# mainBord_old.net
KiCad netlist of a schematic drawn in Altium Designer
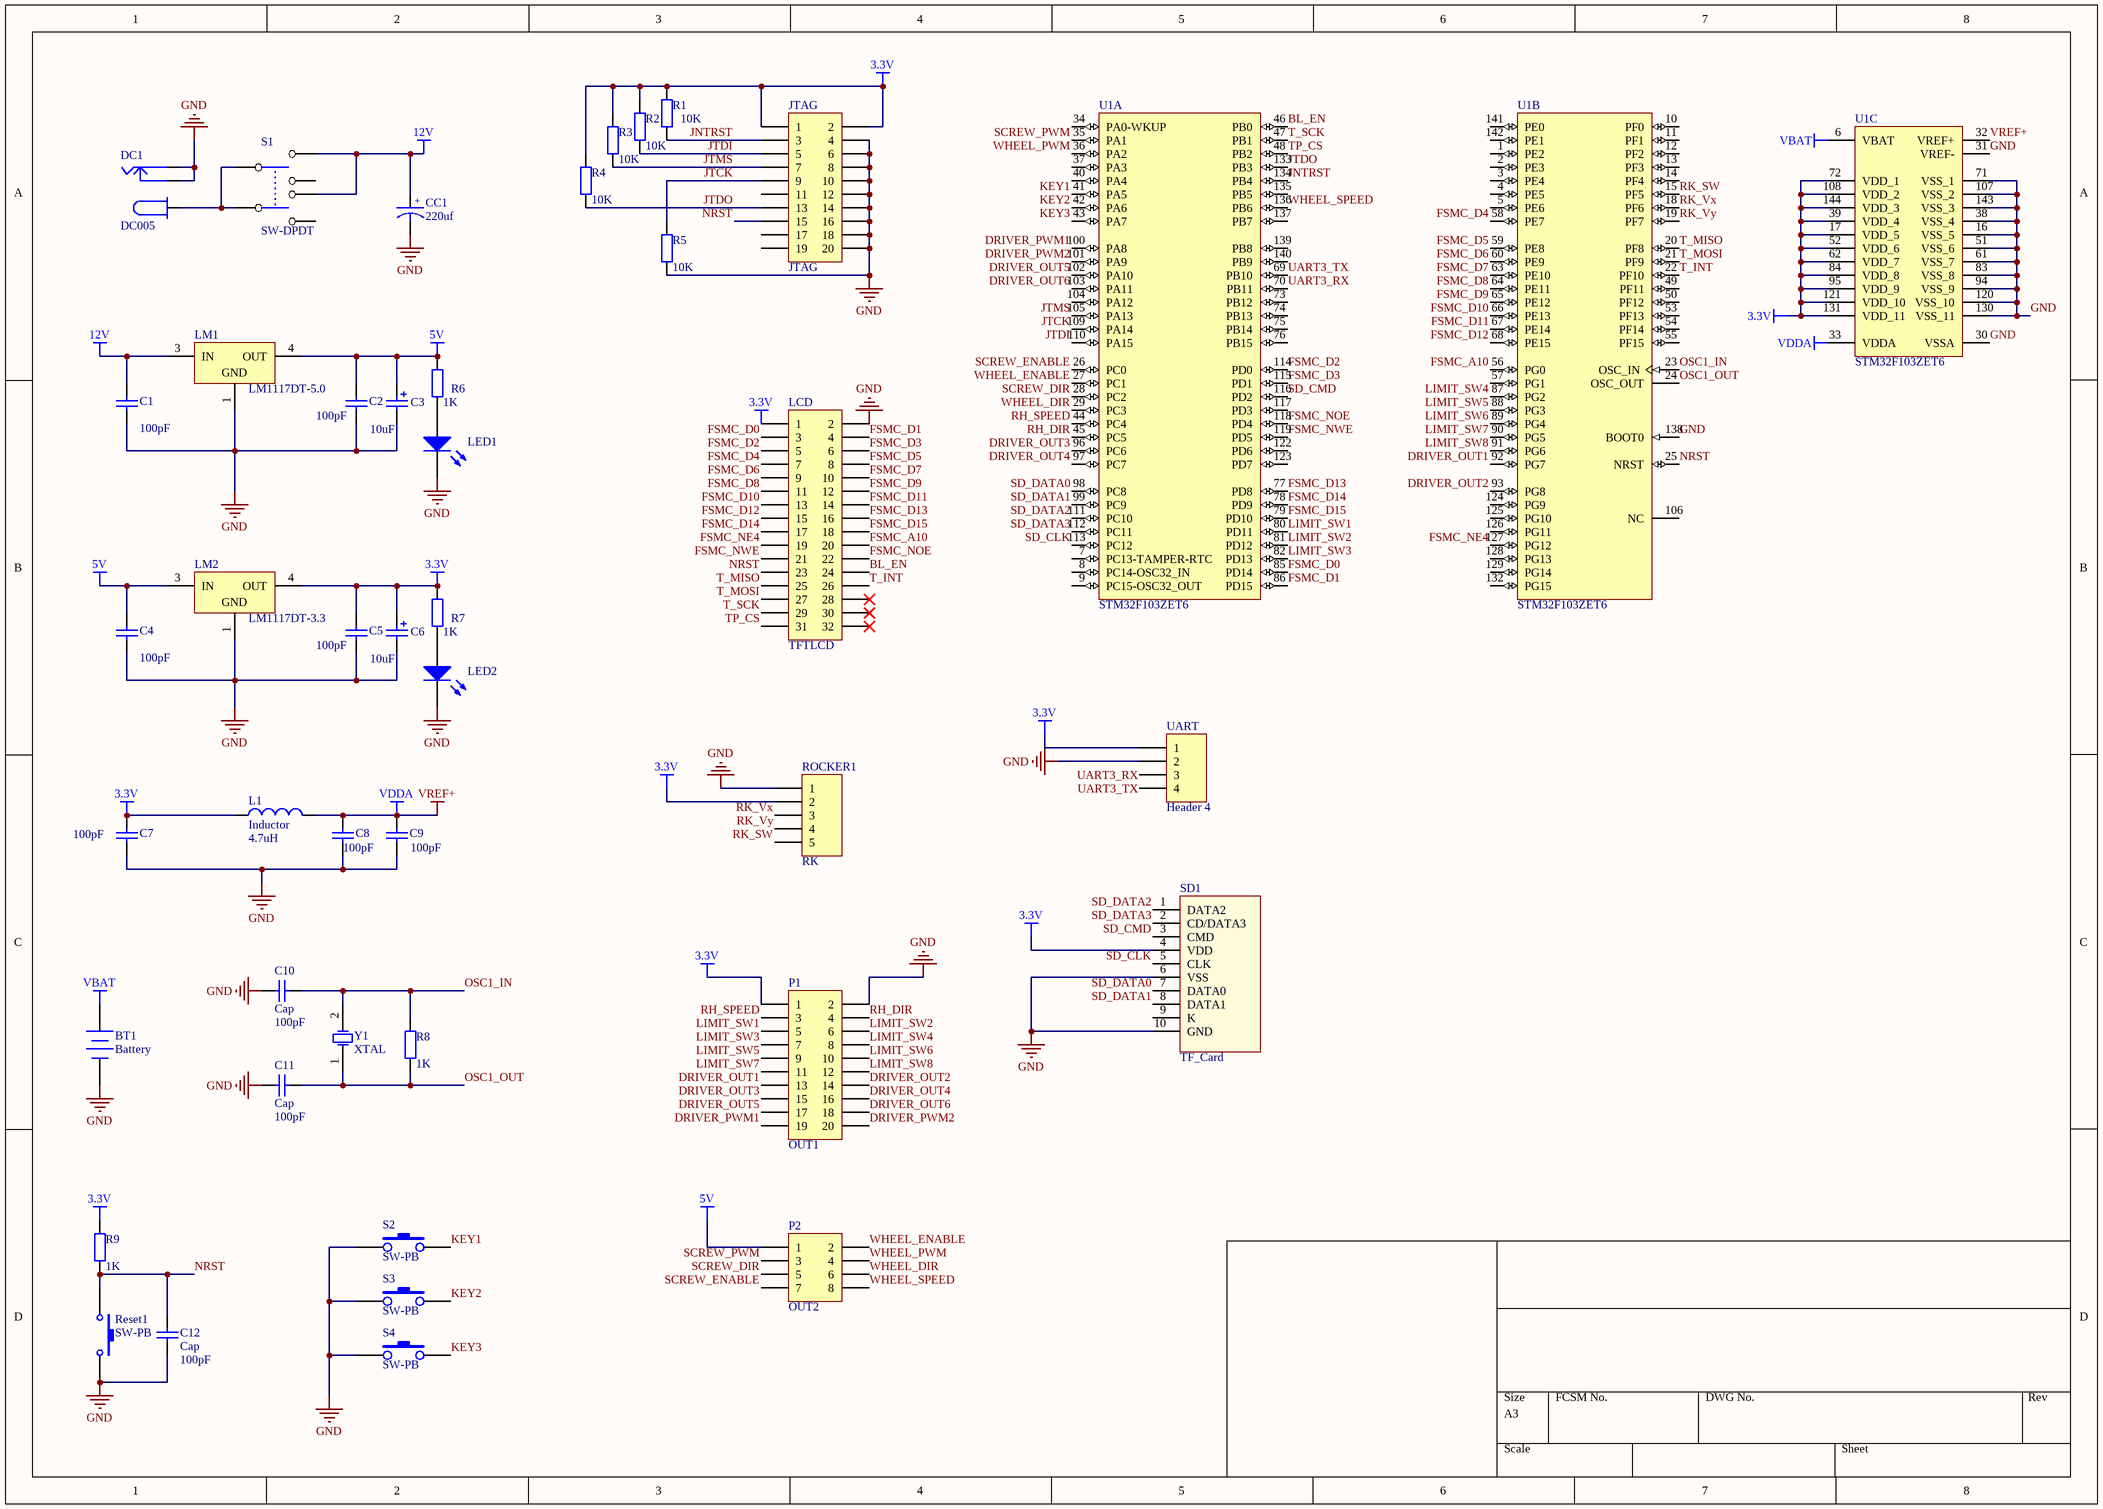
[diagram p0: mainBord_old.SchDoc]

(export (version "E")
  (design (tool "Eeschema 10.0.6"))
  (components
    (comp (ref "BT1")
      (value "Battery")
      (footprint "battery")
      (description "Multicell Battery")
      (fields (field (name "PUBLISHER") "Altium Limited"))
      (libsource (lib "Miscellaneous Devices") (part "Battery"))
    )
    (comp (ref "C1")
      (value "100pF")
      (footprint "C 0805_L")
      (description "Capacitor")
      (fields (field (name "Comment") "Cap") (field (name "PUBLISHER") "Altium Limited"))
      (libsource (lib "Miscellaneous Devices") (part "Cap"))
    )
    (comp (ref "C2")
      (value "100pF")
      (footprint "C 0805_L")
      (description "Capacitor")
      (fields (field (name "Comment") "Cap") (field (name "PUBLISHER") "Altium Limited"))
      (libsource (lib "Miscellaneous Devices") (part "Cap"))
    )
    (comp (ref "C3")
      (value "10uF")
      (footprint "CD A(3216)")
      (description "Polarized Capacitor (Axial)")
      (fields (field (name "Comment") "Cap Pol2") (field (name "PUBLISHER") "Altium Limited"))
      (libsource (lib "Miscellaneous Devices") (part "Cap Pol2"))
    )
    (comp (ref "C4")
      (value "100pF")
      (footprint "C 0805_L")
      (description "Capacitor")
      (fields (field (name "Comment") "Cap") (field (name "PUBLISHER") "Altium Limited"))
      (libsource (lib "Miscellaneous Devices") (part "Cap"))
    )
    (comp (ref "C5")
      (value "100pF")
      (footprint "C 0805_L")
      (description "Capacitor")
      (fields (field (name "Comment") "Cap") (field (name "PUBLISHER") "Altium Limited"))
      (libsource (lib "Miscellaneous Devices") (part "Cap"))
    )
    (comp (ref "C6")
      (value "10uF")
      (footprint "CD A(3216)")
      (description "Polarized Capacitor (Axial)")
      (fields (field (name "Comment") "Cap Pol2") (field (name "PUBLISHER") "Altium Limited"))
      (libsource (lib "Miscellaneous Devices") (part "Cap Pol2"))
    )
    (comp (ref "C7")
      (value "100pF")
      (footprint "C 0805_L")
      (description "Capacitor")
      (fields (field (name "Comment") "Cap") (field (name "PUBLISHER") "Altium Limited"))
      (libsource (lib "Miscellaneous Devices") (part "Cap"))
    )
    (comp (ref "C8")
      (value "100pF")
      (footprint "C 0805_L")
      (description "Capacitor")
      (fields (field (name "Comment") "Cap") (field (name "PUBLISHER") "Altium Limited"))
      (libsource (lib "Miscellaneous Devices") (part "Cap"))
    )
    (comp (ref "C9")
      (value "100pF")
      (footprint "C 0805_L")
      (description "Capacitor")
      (fields (field (name "Comment") "Cap") (field (name "PUBLISHER") "Altium Limited"))
      (libsource (lib "Miscellaneous Devices") (part "Cap"))
    )
    (comp (ref "C10")
      (value "Cap")
      (footprint "C 0805_L")
      (description "Capacitor")
      (fields (field (name "ALTIUM_VALUE") "100pF") (field (name "PUBLISHER") "Altium Limited"))
      (libsource (lib "Miscellaneous Devices") (part "Cap"))
    )
    (comp (ref "C11")
      (value "Cap")
      (footprint "C 0805_L")
      (description "Capacitor")
      (fields (field (name "ALTIUM_VALUE") "100pF") (field (name "PUBLISHER") "Altium Limited"))
      (libsource (lib "Miscellaneous Devices") (part "Cap"))
    )
    (comp (ref "C12")
      (value "Cap")
      (footprint "C 0805_L")
      (description "Capacitor")
      (fields (field (name "ALTIUM_VALUE") "100pF") (field (name "PUBLISHER") "Altium Limited"))
      (libsource (lib "Miscellaneous Devices") (part "Cap"))
    )
    (comp (ref "CC1")
      (value "220uf")
      (footprint "CC88")
      (description "钽电容")
      (libsource (lib "常用器件") (part "CAP-T"))
    )
    (comp (ref "DC1") (value "DC005") (footprint "DC005座") (libsource (lib "myLib") (part "DC005")))
    (comp (ref "JTAG")
      (value "JTAG")
      (footprint "JTAG20")
      (description "Header, 10-Pin, Dual row")
      (fields (field (name "PUBLISHER") "Altium Limited"))
      (libsource (lib "Miscellaneous Connectors") (part "Header 10X2"))
    )
    (comp (ref "L1")
      (value "Inductor")
      (footprint "L 0805")
      (fields (field (name "ALTIUM_VALUE") "4.7uH") (field (name "PUBLISHER") "Altium Limited"))
      (libsource (lib "Miscellaneous Devices") (part "Inductor"))
    )
    (comp (ref "LCD")
      (value "TFTLCD")
      (footprint "HDR2X16")
      (description "Header, 16-Pin, Dual row")
      (fields (field (name "PUBLISHER") "Altium Limited"))
      (libsource (lib "Miscellaneous Connectors") (part "MHDR2X16"))
    )
    (comp (ref "LED1")
      (value "LED2")
      (footprint "LED-0805")
      (description "Typical RED, GREEN, YELLOW, AMBER GaAs LED")
      (fields (field (name "PUBLISHER") "Altium Limited"))
      (libsource (lib "Miscellaneous Devices") (part "LED2"))
    )
    (comp (ref "LED2")
      (value "LED2")
      (footprint "LED-0805")
      (description "Typical RED, GREEN, YELLOW, AMBER GaAs LED")
      (fields (field (name "PUBLISHER") "Altium Limited"))
      (libsource (lib "Miscellaneous Devices") (part "LED2"))
    )
    (comp (ref "LM1")
      (value "LM1117DT-5.0")
      (footprint "SOT-223")
      (description "800mA Low-Dropout Linear Regulator, 3-pin TO-252")
      (fields (field (name "MANUFACTURER") "National Semiconductor"))
      (libsource (lib "National Semiconductor LDO") (part "LM1117DT-5.0"))
    )
    (comp (ref "LM2")
      (value "LM1117DT-3.3")
      (footprint "SOT-223")
      (description "800mA Low-Dropout Linear Regulator, 3-pin TO-252")
      (fields (field (name "MANUFACTURER") "National Semiconductor"))
      (libsource (lib "National Semiconductor LDO") (part "LM1117DT-3.3"))
    )
    (comp (ref "P1")
      (value "OUT1")
      (footprint "JTAG20")
      (description "Header, 10-Pin, Dual row")
      (fields (field (name "PUBLISHER") "Altium Limited"))
      (libsource (lib "Miscellaneous Connectors") (part "Header 10X2"))
    )
    (comp (ref "P2")
      (value "OUT2")
      (footprint "HDR2X4")
      (description "Header, 4-Pin, Dual row")
      (fields (field (name "PUBLISHER") "Altium Limited"))
      (libsource (lib "Miscellaneous Connectors") (part "Header 4X2"))
    )
    (comp (ref "R1")
      (value "10K")
      (footprint "R 0805_L")
      (description "Resistor")
      (fields (field (name "Comment") "Res2") (field (name "PUBLISHER") "Altium Limited"))
      (libsource (lib "Miscellaneous Devices") (part "Res2"))
    )
    (comp (ref "R2")
      (value "10K")
      (footprint "R 0805_L")
      (description "Resistor")
      (fields (field (name "PUBLISHER") "Altium Limited"))
      (libsource (lib "Miscellaneous Devices") (part "Res2"))
    )
    (comp (ref "R3")
      (value "10K")
      (footprint "R 0805_L")
      (description "Resistor")
      (fields (field (name "Comment") "Res2") (field (name "PUBLISHER") "Altium Limited"))
      (libsource (lib "Miscellaneous Devices") (part "Res2"))
    )
    (comp (ref "R4")
      (value "10K")
      (footprint "R 0805_L")
      (description "Resistor")
      (fields (field (name "Comment") "Res2") (field (name "PUBLISHER") "Altium Limited"))
      (libsource (lib "Miscellaneous Devices") (part "Res2"))
    )
    (comp (ref "R5")
      (value "10K")
      (footprint "R 0805_L")
      (description "Resistor")
      (fields (field (name "Comment") "Res2") (field (name "PUBLISHER") "Altium Limited"))
      (libsource (lib "Miscellaneous Devices") (part "Res2"))
    )
    (comp (ref "R6")
      (value "1K")
      (footprint "R 0805_L")
      (description "Resistor")
      (fields (field (name "Comment") "Res2") (field (name "PUBLISHER") "Altium Limited"))
      (libsource (lib "Miscellaneous Devices") (part "Res2"))
    )
    (comp (ref "R7")
      (value "1K")
      (footprint "R 0805_L")
      (description "Resistor")
      (fields (field (name "Comment") "Res2") (field (name "PUBLISHER") "Altium Limited"))
      (libsource (lib "Miscellaneous Devices") (part "Res2"))
    )
    (comp (ref "R8")
      (value "1K")
      (footprint "R 0805_L")
      (description "Resistor")
      (fields (field (name "Comment") "Res2") (field (name "PUBLISHER") "Altium Limited"))
      (libsource (lib "Miscellaneous Devices") (part "Res2"))
    )
    (comp (ref "R9")
      (value "1K")
      (footprint "R 0805_L")
      (description "Resistor")
      (fields (field (name "Comment") "Res2") (field (name "PUBLISHER") "Altium Limited"))
      (libsource (lib "Miscellaneous Devices") (part "Res2"))
    )
    (comp (ref "Reset1")
      (value "SW-PB")
      (footprint "微动开关-1")
      (description "Switch")
      (fields (field (name "PUBLISHER") "Altium Limited"))
      (libsource (lib "Miscellaneous Devices") (part "SW-PB"))
    )
    (comp (ref "ROCKER1")
      (value "RK")
      (footprint "HDR2.54-M-LI-5P")
      (description "Header, 5-Pin")
      (fields (field (name "PUBLISHER") "Altium Limited"))
      (libsource (lib "Miscellaneous Connectors") (part "MHDR1X5"))
    )
    (comp (ref "S1") (value "SW-DPDT") (footprint "按键开关-1") (libsource (lib "常用器件") (part "SW-DPDT")))
    (comp (ref "S2") (value "SW-PB") (footprint "微动开关-大-1-绿") (libsource (lib "常用器件") (part "微动开关")))
    (comp (ref "S3") (value "SW-PB") (footprint "微动开关-大-1-绿") (libsource (lib "常用器件") (part "微动开关")))
    (comp (ref "S4") (value "SW-PB") (footprint "微动开关-大-1-绿") (libsource (lib "常用器件") (part "微动开关")))
    (comp (ref "SD1")
      (value "TF_Card")
      (footprint "Micro SD")
      (description "TF卡座")
      (fields (field (name "版权归属") "源创客"))
      (libsource (lib "4.1   - 接口类") (part "TF_Card"))
    )
    (comp (ref "U1")
      (value "STM32F103ZET6")
      (footprint "STM-LQFP144_N")
      (libsource (lib "STMicroelectronics STM32 F1") (part "STM32F103ZET6"))
    )
    (comp (ref "UART")
      (value "Header 4")
      (footprint "HDR2.54-LI-4P")
      (description "Header, 4-Pin")
      (fields (field (name "PUBLISHER") "Altium Limited"))
      (libsource (lib "Miscellaneous Connectors") (part "Header 4"))
    )
    (comp (ref "Y1")
      (value "XTAL")
      (footprint "HC-49S")
      (description "Crystal Oscillator")
      (fields (field (name "PUBLISHER") "Altium Limited"))
      (libsource (lib "Miscellaneous Devices") (part "XTAL"))
    )
  )
  (nets
    (net (code "1") (name "/BL_EN") (class "Default")
      (node (ref "LCD") (pin "24") (pinfunction "24_24") (pintype "passive"))
      (node (ref "U1") (pin "46") (pinfunction "PB0_46") (pintype "bidirectional"))
    )
    (net (code "2") (name "/DRIVER_OUT1") (class "Default")
      (node (ref "P1") (pin "13") (pinfunction "13_13") (pintype "passive"))
      (node (ref "U1") (pin "92") (pinfunction "PG7_92") (pintype "bidirectional"))
    )
    (net (code "3") (name "/DRIVER_OUT2") (class "Default")
      (node (ref "P1") (pin "14") (pinfunction "14_14") (pintype "passive"))
      (node (ref "U1") (pin "93") (pinfunction "PG8_93") (pintype "bidirectional"))
    )
    (net (code "4") (name "/DRIVER_OUT3") (class "Default")
      (node (ref "P1") (pin "15") (pinfunction "15_15") (pintype "passive"))
      (node (ref "U1") (pin "96") (pinfunction "PC6_96") (pintype "bidirectional"))
    )
    (net (code "5") (name "/DRIVER_OUT4") (class "Default")
      (node (ref "P1") (pin "16") (pinfunction "16_16") (pintype "passive"))
      (node (ref "U1") (pin "97") (pinfunction "PC7_97") (pintype "bidirectional"))
    )
    (net (code "6") (name "/DRIVER_OUT5") (class "Default")
      (node (ref "P1") (pin "17") (pinfunction "17_17") (pintype "passive"))
      (node (ref "U1") (pin "102") (pinfunction "PA10_102") (pintype "bidirectional"))
    )
    (net (code "7") (name "/DRIVER_OUT6") (class "Default")
      (node (ref "P1") (pin "18") (pinfunction "18_18") (pintype "passive"))
      (node (ref "U1") (pin "103") (pinfunction "PA11_103") (pintype "bidirectional"))
    )
    (net (code "8") (name "/DRIVER_PWM1") (class "Default")
      (node (ref "P1") (pin "19") (pinfunction "19_19") (pintype "passive"))
      (node (ref "U1") (pin "100") (pinfunction "PA8_100") (pintype "bidirectional"))
    )
    (net (code "9") (name "/DRIVER_PWM2") (class "Default")
      (node (ref "P1") (pin "20") (pinfunction "20_20") (pintype "passive"))
      (node (ref "U1") (pin "101") (pinfunction "PA9_101") (pintype "bidirectional"))
    )
    (net (code "10") (name "/FSMC_A10") (class "Default")
      (node (ref "LCD") (pin "20") (pinfunction "20_20") (pintype "passive"))
      (node (ref "U1") (pin "56") (pinfunction "PG0_56") (pintype "bidirectional"))
    )
    (net (code "11") (name "/FSMC_D0") (class "Default")
      (node (ref "LCD") (pin "3") (pinfunction "3_3") (pintype "passive"))
      (node (ref "U1") (pin "85") (pinfunction "PD14_85") (pintype "bidirectional"))
    )
    (net (code "12") (name "/FSMC_D1") (class "Default")
      (node (ref "LCD") (pin "4") (pinfunction "4_4") (pintype "passive"))
      (node (ref "U1") (pin "86") (pinfunction "PD15_86") (pintype "bidirectional"))
    )
    (net (code "13") (name "/FSMC_D2") (class "Default")
      (node (ref "LCD") (pin "5") (pinfunction "5_5") (pintype "passive"))
      (node (ref "U1") (pin "114") (pinfunction "PD0_114") (pintype "bidirectional"))
    )
    (net (code "14") (name "/FSMC_D3") (class "Default")
      (node (ref "LCD") (pin "6") (pinfunction "6_6") (pintype "passive"))
      (node (ref "U1") (pin "115") (pinfunction "PD1_115") (pintype "bidirectional"))
    )
    (net (code "15") (name "/FSMC_D4") (class "Default")
      (node (ref "LCD") (pin "7") (pinfunction "7_7") (pintype "passive"))
      (node (ref "U1") (pin "58") (pinfunction "PE7_58") (pintype "bidirectional"))
    )
    (net (code "16") (name "/FSMC_D5") (class "Default")
      (node (ref "LCD") (pin "8") (pinfunction "8_8") (pintype "passive"))
      (node (ref "U1") (pin "59") (pinfunction "PE8_59") (pintype "bidirectional"))
    )
    (net (code "17") (name "/FSMC_D6") (class "Default")
      (node (ref "LCD") (pin "9") (pinfunction "9_9") (pintype "passive"))
      (node (ref "U1") (pin "60") (pinfunction "PE9_60") (pintype "bidirectional"))
    )
    (net (code "18") (name "/FSMC_D7") (class "Default")
      (node (ref "LCD") (pin "10") (pinfunction "10_10") (pintype "passive"))
      (node (ref "U1") (pin "63") (pinfunction "PE10_63") (pintype "bidirectional"))
    )
    (net (code "19") (name "/FSMC_D8") (class "Default")
      (node (ref "LCD") (pin "11") (pinfunction "11_11") (pintype "passive"))
      (node (ref "U1") (pin "64") (pinfunction "PE11_64") (pintype "bidirectional"))
    )
    (net (code "20") (name "/FSMC_D9") (class "Default")
      (node (ref "LCD") (pin "12") (pinfunction "12_12") (pintype "passive"))
      (node (ref "U1") (pin "65") (pinfunction "PE12_65") (pintype "bidirectional"))
    )
    (net (code "21") (name "/FSMC_D10") (class "Default")
      (node (ref "LCD") (pin "13") (pinfunction "13_13") (pintype "passive"))
      (node (ref "U1") (pin "66") (pinfunction "PE13_66") (pintype "bidirectional"))
    )
    (net (code "22") (name "/FSMC_D11") (class "Default")
      (node (ref "LCD") (pin "14") (pinfunction "14_14") (pintype "passive"))
      (node (ref "U1") (pin "67") (pinfunction "PE14_67") (pintype "bidirectional"))
    )
    (net (code "23") (name "/FSMC_D12") (class "Default")
      (node (ref "LCD") (pin "15") (pinfunction "15_15") (pintype "passive"))
      (node (ref "U1") (pin "68") (pinfunction "PE15_68") (pintype "bidirectional"))
    )
    (net (code "24") (name "/FSMC_D13") (class "Default")
      (node (ref "LCD") (pin "16") (pinfunction "16_16") (pintype "passive"))
      (node (ref "U1") (pin "77") (pinfunction "PD8_77") (pintype "bidirectional"))
    )
    (net (code "25") (name "/FSMC_D14") (class "Default")
      (node (ref "LCD") (pin "17") (pinfunction "17_17") (pintype "passive"))
      (node (ref "U1") (pin "78") (pinfunction "PD9_78") (pintype "bidirectional"))
    )
    (net (code "26") (name "/FSMC_D15") (class "Default")
      (node (ref "LCD") (pin "18") (pinfunction "18_18") (pintype "passive"))
      (node (ref "U1") (pin "79") (pinfunction "PD10_79") (pintype "bidirectional"))
    )
    (net (code "27") (name "/FSMC_NE4") (class "Default")
      (node (ref "LCD") (pin "19") (pinfunction "19_19") (pintype "passive"))
      (node (ref "U1") (pin "127") (pinfunction "PG12_127") (pintype "bidirectional"))
    )
    (net (code "28") (name "/FSMC_NOE") (class "Default")
      (node (ref "LCD") (pin "22") (pinfunction "22_22") (pintype "passive"))
      (node (ref "U1") (pin "118") (pinfunction "PD4_118") (pintype "bidirectional"))
    )
    (net (code "29") (name "/FSMC_NWE") (class "Default")
      (node (ref "LCD") (pin "21") (pinfunction "21_21") (pintype "passive"))
      (node (ref "U1") (pin "119") (pinfunction "PD5_119") (pintype "bidirectional"))
    )
    (net (code "30") (name "/JNTRST") (class "Default")
      (node (ref "JTAG") (pin "3") (pinfunction "3_3") (pintype "passive"))
      (node (ref "R1") (pin "1") (pinfunction "1_1") (pintype "passive"))
      (node (ref "U1") (pin "134") (pinfunction "PB4_134") (pintype "bidirectional"))
    )
    (net (code "31") (name "/JTCK") (class "Default")
      (node (ref "JTAG") (pin "9") (pinfunction "9_9") (pintype "passive"))
      (node (ref "R5") (pin "2") (pinfunction "2_2") (pintype "passive"))
      (node (ref "U1") (pin "109") (pinfunction "PA14_109") (pintype "bidirectional"))
    )
    (net (code "32") (name "/JTDI") (class "Default")
      (node (ref "JTAG") (pin "5") (pinfunction "5_5") (pintype "passive"))
      (node (ref "R2") (pin "1") (pinfunction "1_1") (pintype "passive"))
      (node (ref "U1") (pin "110") (pinfunction "PA15_110") (pintype "bidirectional"))
    )
    (net (code "33") (name "/JTDO") (class "Default")
      (node (ref "JTAG") (pin "13") (pinfunction "13_13") (pintype "passive"))
      (node (ref "R4") (pin "1") (pinfunction "1_1") (pintype "passive"))
      (node (ref "U1") (pin "133") (pinfunction "PB3_133") (pintype "bidirectional"))
    )
    (net (code "34") (name "/JTMS") (class "Default")
      (node (ref "JTAG") (pin "7") (pinfunction "7_7") (pintype "passive"))
      (node (ref "R3") (pin "1") (pinfunction "1_1") (pintype "passive"))
      (node (ref "U1") (pin "105") (pinfunction "PA13_105") (pintype "bidirectional"))
    )
    (net (code "35") (name "/KEY1") (class "Default")
      (node (ref "S2") (pin "2") (pinfunction "2_2") (pintype "passive"))
      (node (ref "U1") (pin "41") (pinfunction "PA5_41") (pintype "bidirectional"))
    )
    (net (code "36") (name "/KEY2") (class "Default")
      (node (ref "S3") (pin "2") (pinfunction "2_2") (pintype "passive"))
      (node (ref "U1") (pin "42") (pinfunction "PA6_42") (pintype "bidirectional"))
    )
    (net (code "37") (name "/KEY3") (class "Default")
      (node (ref "S4") (pin "2") (pinfunction "2_2") (pintype "passive"))
      (node (ref "U1") (pin "43") (pinfunction "PA7_43") (pintype "bidirectional"))
    )
    (net (code "38") (name "/LIMIT_SW1") (class "Default")
      (node (ref "P1") (pin "5") (pinfunction "5_5") (pintype "passive"))
      (node (ref "U1") (pin "80") (pinfunction "PD11_80") (pintype "bidirectional"))
    )
    (net (code "39") (name "/LIMIT_SW2") (class "Default")
      (node (ref "P1") (pin "6") (pinfunction "6_6") (pintype "passive"))
      (node (ref "U1") (pin "81") (pinfunction "PD12_81") (pintype "bidirectional"))
    )
    (net (code "40") (name "/LIMIT_SW3") (class "Default")
      (node (ref "P1") (pin "7") (pinfunction "7_7") (pintype "passive"))
      (node (ref "U1") (pin "82") (pinfunction "PD13_82") (pintype "bidirectional"))
    )
    (net (code "41") (name "/LIMIT_SW4") (class "Default")
      (node (ref "P1") (pin "8") (pinfunction "8_8") (pintype "passive"))
      (node (ref "U1") (pin "87") (pinfunction "PG2_87") (pintype "bidirectional"))
    )
    (net (code "42") (name "/LIMIT_SW5") (class "Default")
      (node (ref "P1") (pin "9") (pinfunction "9_9") (pintype "passive"))
      (node (ref "U1") (pin "88") (pinfunction "PG3_88") (pintype "bidirectional"))
    )
    (net (code "43") (name "/LIMIT_SW6") (class "Default")
      (node (ref "P1") (pin "10") (pinfunction "10_10") (pintype "passive"))
      (node (ref "U1") (pin "89") (pinfunction "PG4_89") (pintype "bidirectional"))
    )
    (net (code "44") (name "/LIMIT_SW7") (class "Default")
      (node (ref "P1") (pin "11") (pinfunction "11_11") (pintype "passive"))
      (node (ref "U1") (pin "90") (pinfunction "PG5_90") (pintype "bidirectional"))
    )
    (net (code "45") (name "/LIMIT_SW8") (class "Default")
      (node (ref "P1") (pin "12") (pinfunction "12_12") (pintype "passive"))
      (node (ref "U1") (pin "91") (pinfunction "PG6_91") (pintype "bidirectional"))
    )
    (net (code "46") (name "/NRST") (class "Default")
      (node (ref "C12") (pin "1") (pinfunction "1_1") (pintype "passive"))
      (node (ref "JTAG") (pin "15") (pinfunction "15_15") (pintype "passive"))
      (node (ref "LCD") (pin "23") (pinfunction "23_23") (pintype "passive"))
      (node (ref "R9") (pin "1") (pinfunction "1_1") (pintype "passive"))
      (node (ref "Reset1") (pin "1") (pinfunction "1_1") (pintype "passive"))
      (node (ref "U1") (pin "25") (pinfunction "NRST_25") (pintype "bidirectional"))
    )
    (net (code "47") (name "/OSC1_IN") (class "Default")
      (node (ref "C10") (pin "1") (pinfunction "1_1") (pintype "passive"))
      (node (ref "R8") (pin "2") (pinfunction "2_2") (pintype "passive"))
      (node (ref "U1") (pin "23") (pinfunction "OSC_IN_23") (pintype "input"))
      (node (ref "Y1") (pin "2") (pinfunction "OSC2_2") (pintype "passive"))
    )
    (net (code "48") (name "/OSC1_OUT") (class "Default")
      (node (ref "C11") (pin "1") (pinfunction "1_1") (pintype "passive"))
      (node (ref "R8") (pin "1") (pinfunction "1_1") (pintype "passive"))
      (node (ref "U1") (pin "24") (pinfunction "OSC_OUT_24") (pintype "passive"))
      (node (ref "Y1") (pin "1") (pinfunction "OSC1_1") (pintype "passive"))
    )
    (net (code "49") (name "/RH_DIR") (class "Default")
      (node (ref "P1") (pin "4") (pinfunction "4_4") (pintype "passive"))
      (node (ref "U1") (pin "45") (pinfunction "PC5_45") (pintype "bidirectional"))
    )
    (net (code "50") (name "/RH_SPEED") (class "Default")
      (node (ref "P1") (pin "3") (pinfunction "3_3") (pintype "passive"))
      (node (ref "U1") (pin "44") (pinfunction "PC4_44") (pintype "bidirectional"))
    )
    (net (code "51") (name "/RK_SW") (class "Default")
      (node (ref "ROCKER1") (pin "5") (pinfunction "5_5") (pintype "passive"))
      (node (ref "U1") (pin "15") (pinfunction "PF5_15") (pintype "bidirectional"))
    )
    (net (code "52") (name "/RK_Vx") (class "Default")
      (node (ref "ROCKER1") (pin "3") (pinfunction "3_3") (pintype "passive"))
      (node (ref "U1") (pin "18") (pinfunction "PF6_18") (pintype "bidirectional"))
    )
    (net (code "53") (name "/RK_Vy") (class "Default")
      (node (ref "ROCKER1") (pin "4") (pinfunction "4_4") (pintype "passive"))
      (node (ref "U1") (pin "19") (pinfunction "PF7_19") (pintype "bidirectional"))
    )
    (net (code "54") (name "/SCREW_DIR") (class "Default")
      (node (ref "P2") (pin "5") (pinfunction "5_5") (pintype "passive"))
      (node (ref "U1") (pin "28") (pinfunction "PC2_28") (pintype "bidirectional"))
    )
    (net (code "55") (name "/SCREW_ENABLE") (class "Default")
      (node (ref "P2") (pin "7") (pinfunction "7_7") (pintype "passive"))
      (node (ref "U1") (pin "26") (pinfunction "PC0_26") (pintype "bidirectional"))
    )
    (net (code "56") (name "/SCREW_PWM") (class "Default")
      (node (ref "P2") (pin "3") (pinfunction "3_3") (pintype "passive"))
      (node (ref "U1") (pin "35") (pinfunction "PA1_35") (pintype "bidirectional"))
    )
    (net (code "57") (name "/SD_CLK") (class "Default")
      (node (ref "SD1") (pin "5") (pinfunction "CLK_5") (pintype "passive"))
      (node (ref "U1") (pin "113") (pinfunction "PC12_113") (pintype "bidirectional"))
    )
    (net (code "58") (name "/SD_CMD") (class "Default")
      (node (ref "SD1") (pin "3") (pinfunction "CMD_3") (pintype "passive"))
      (node (ref "U1") (pin "116") (pinfunction "PD2_116") (pintype "bidirectional"))
    )
    (net (code "59") (name "/SD_DATA0") (class "Default")
      (node (ref "SD1") (pin "7") (pinfunction "DATA0_7") (pintype "passive"))
      (node (ref "U1") (pin "98") (pinfunction "PC8_98") (pintype "bidirectional"))
    )
    (net (code "60") (name "/SD_DATA1") (class "Default")
      (node (ref "SD1") (pin "8") (pinfunction "DATA1_8") (pintype "passive"))
      (node (ref "U1") (pin "99") (pinfunction "PC9_99") (pintype "bidirectional"))
    )
    (net (code "61") (name "/SD_DATA2") (class "Default")
      (node (ref "SD1") (pin "1") (pinfunction "DATA2_1") (pintype "passive"))
      (node (ref "U1") (pin "111") (pinfunction "PC10_111") (pintype "bidirectional"))
    )
    (net (code "62") (name "/SD_DATA3") (class "Default")
      (node (ref "SD1") (pin "2") (pinfunction "CD/DATA3_2") (pintype "passive"))
      (node (ref "U1") (pin "112") (pinfunction "PC11_112") (pintype "bidirectional"))
    )
    (net (code "63") (name "/TP_CS") (class "Default")
      (node (ref "LCD") (pin "31") (pinfunction "31_31") (pintype "passive"))
      (node (ref "U1") (pin "48") (pinfunction "PB2_48") (pintype "bidirectional"))
    )
    (net (code "64") (name "/T_INT") (class "Default")
      (node (ref "LCD") (pin "26") (pinfunction "26_26") (pintype "passive"))
      (node (ref "U1") (pin "22") (pinfunction "PF10_22") (pintype "bidirectional"))
    )
    (net (code "65") (name "/T_MISO") (class "Default")
      (node (ref "LCD") (pin "25") (pinfunction "25_25") (pintype "passive"))
      (node (ref "U1") (pin "20") (pinfunction "PF8_20") (pintype "bidirectional"))
    )
    (net (code "66") (name "/T_MOSI") (class "Default")
      (node (ref "LCD") (pin "27") (pinfunction "27_27") (pintype "passive"))
      (node (ref "U1") (pin "21") (pinfunction "PF9_21") (pintype "bidirectional"))
    )
    (net (code "67") (name "/T_SCK") (class "Default")
      (node (ref "LCD") (pin "29") (pinfunction "29_29") (pintype "passive"))
      (node (ref "U1") (pin "47") (pinfunction "PB1_47") (pintype "bidirectional"))
    )
    (net (code "68") (name "/UART3_RX") (class "Default")
      (node (ref "U1") (pin "70") (pinfunction "PB11_70") (pintype "bidirectional"))
      (node (ref "UART") (pin "3") (pinfunction "3_3") (pintype "passive"))
    )
    (net (code "69") (name "/UART3_TX") (class "Default")
      (node (ref "U1") (pin "69") (pinfunction "PB10_69") (pintype "bidirectional"))
      (node (ref "UART") (pin "4") (pinfunction "4_4") (pintype "passive"))
    )
    (net (code "70") (name "/WHEEL_DIR") (class "Default")
      (node (ref "P2") (pin "6") (pinfunction "6_6") (pintype "passive"))
      (node (ref "U1") (pin "29") (pinfunction "PC3_29") (pintype "bidirectional"))
    )
    (net (code "71") (name "/WHEEL_ENABLE") (class "Default")
      (node (ref "P2") (pin "2") (pinfunction "2_2") (pintype "passive"))
      (node (ref "U1") (pin "27") (pinfunction "PC1_27") (pintype "bidirectional"))
    )
    (net (code "72") (name "/WHEEL_PWM") (class "Default")
      (node (ref "P2") (pin "4") (pinfunction "4_4") (pintype "passive"))
      (node (ref "U1") (pin "36") (pinfunction "PA2_36") (pintype "bidirectional"))
    )
    (net (code "73") (name "/WHEEL_SPEED") (class "Default")
      (node (ref "P2") (pin "8") (pinfunction "8_8") (pintype "passive"))
      (node (ref "U1") (pin "136") (pinfunction "PB6_136") (pintype "bidirectional"))
    )
    (net (code "74") (name "3.3V") (class "Default")
      (node (ref "C5") (pin "2") (pinfunction "2_2") (pintype "passive"))
      (node (ref "C6") (pin "1") (pinfunction "1_1") (pintype "passive"))
      (node (ref "C7") (pin "2") (pinfunction "2_2") (pintype "passive"))
      (node (ref "JTAG") (pin "1") (pinfunction "1_1") (pintype "passive"))
      (node (ref "JTAG") (pin "2") (pinfunction "2_2") (pintype "passive"))
      (node (ref "L1") (pin "1") (pinfunction "1_1") (pintype "passive"))
      (node (ref "LCD") (pin "1") (pinfunction "1_1") (pintype "passive"))
      (node (ref "LM2") (pin "4") (pinfunction "OUT_4") (pintype "power_in"))
      (node (ref "P1") (pin "1") (pinfunction "1_1") (pintype "passive"))
      (node (ref "R1") (pin "2") (pinfunction "2_2") (pintype "passive"))
      (node (ref "R2") (pin "2") (pinfunction "2_2") (pintype "passive"))
      (node (ref "R3") (pin "2") (pinfunction "2_2") (pintype "passive"))
      (node (ref "R4") (pin "2") (pinfunction "2_2") (pintype "passive"))
      (node (ref "R7") (pin "2") (pinfunction "2_2") (pintype "passive"))
      (node (ref "R9") (pin "2") (pinfunction "2_2") (pintype "passive"))
      (node (ref "ROCKER1") (pin "2") (pinfunction "2_2") (pintype "passive"))
      (node (ref "SD1") (pin "4") (pinfunction "VDD_4") (pintype "passive"))
      (node (ref "U1") (pin "108") (pinfunction "VDD_2_108") (pintype "power_in"))
      (node (ref "U1") (pin "121") (pinfunction "VDD_10_121") (pintype "power_in"))
      (node (ref "U1") (pin "131") (pinfunction "VDD_11_131") (pintype "power_in"))
      (node (ref "U1") (pin "144") (pinfunction "VDD_3_144") (pintype "power_in"))
      (node (ref "U1") (pin "17") (pinfunction "VDD_5_17") (pintype "power_in"))
      (node (ref "U1") (pin "39") (pinfunction "VDD_4_39") (pintype "power_in"))
      (node (ref "U1") (pin "52") (pinfunction "VDD_6_52") (pintype "power_in"))
      (node (ref "U1") (pin "62") (pinfunction "VDD_7_62") (pintype "power_in"))
      (node (ref "U1") (pin "72") (pinfunction "VDD_1_72") (pintype "power_in"))
      (node (ref "U1") (pin "84") (pinfunction "VDD_8_84") (pintype "power_in"))
      (node (ref "U1") (pin "95") (pinfunction "VDD_9_95") (pintype "power_in"))
      (node (ref "UART") (pin "1") (pinfunction "1_1") (pintype "passive"))
    )
    (net (code "75") (name "5V") (class "Default")
      (node (ref "C2") (pin "2") (pinfunction "2_2") (pintype "passive"))
      (node (ref "C3") (pin "1") (pinfunction "1_1") (pintype "passive"))
      (node (ref "C4") (pin "2") (pinfunction "2_2") (pintype "passive"))
      (node (ref "LM1") (pin "4") (pinfunction "OUT_4") (pintype "power_in"))
      (node (ref "LM2") (pin "3") (pinfunction "IN_3") (pintype "power_in"))
      (node (ref "P2") (pin "1") (pinfunction "1_1") (pintype "passive"))
      (node (ref "R6") (pin "2") (pinfunction "2_2") (pintype "passive"))
    )
    (net (code "76") (name "12V") (class "Default")
      (node (ref "C1") (pin "2") (pinfunction "2_2") (pintype "passive"))
      (node (ref "CC1") (pin "1") (pinfunction "1_1") (pintype "passive"))
      (node (ref "LM1") (pin "3") (pinfunction "IN_3") (pintype "power_in"))
      (node (ref "S1") (pin "2") (pinfunction "2_2") (pintype "passive"))
      (node (ref "S1") (pin "5") (pinfunction "5_5") (pintype "passive"))
    )
    (net (code "77") (name "GND") (class "Default")
      (node (ref "BT1") (pin "2") (pinfunction "-_2") (pintype "passive"))
      (node (ref "C1") (pin "1") (pinfunction "1_1") (pintype "passive"))
      (node (ref "C10") (pin "2") (pinfunction "2_2") (pintype "passive"))
      (node (ref "C11") (pin "2") (pinfunction "2_2") (pintype "passive"))
      (node (ref "C12") (pin "2") (pinfunction "2_2") (pintype "passive"))
      (node (ref "C2") (pin "1") (pinfunction "1_1") (pintype "passive"))
      (node (ref "C3") (pin "2") (pinfunction "2_2") (pintype "passive"))
      (node (ref "C4") (pin "1") (pinfunction "1_1") (pintype "passive"))
      (node (ref "C5") (pin "1") (pinfunction "1_1") (pintype "passive"))
      (node (ref "C6") (pin "2") (pinfunction "2_2") (pintype "passive"))
      (node (ref "C7") (pin "1") (pinfunction "1_1") (pintype "passive"))
      (node (ref "C8") (pin "1") (pinfunction "1_1") (pintype "passive"))
      (node (ref "C9") (pin "1") (pinfunction "1_1") (pintype "passive"))
      (node (ref "CC1") (pin "2") (pinfunction "2_2") (pintype "passive"))
      (node (ref "DC1") (pin "CON") (pinfunction "SW_CON") (pintype "passive"))
      (node (ref "DC1") (pin "GND") (pinfunction "6_GND") (pintype "passive"))
      (node (ref "JTAG") (pin "10") (pinfunction "10_10") (pintype "passive"))
      (node (ref "JTAG") (pin "12") (pinfunction "12_12") (pintype "passive"))
      (node (ref "JTAG") (pin "14") (pinfunction "14_14") (pintype "passive"))
      (node (ref "JTAG") (pin "16") (pinfunction "16_16") (pintype "passive"))
      (node (ref "JTAG") (pin "18") (pinfunction "18_18") (pintype "passive"))
      (node (ref "JTAG") (pin "20") (pinfunction "20_20") (pintype "passive"))
      (node (ref "JTAG") (pin "4") (pinfunction "4_4") (pintype "passive"))
      (node (ref "JTAG") (pin "6") (pinfunction "6_6") (pintype "passive"))
      (node (ref "JTAG") (pin "8") (pinfunction "8_8") (pintype "passive"))
      (node (ref "LCD") (pin "2") (pinfunction "2_2") (pintype "passive"))
      (node (ref "LED1") (pin "2") (pinfunction "K_2") (pintype "passive"))
      (node (ref "LED2") (pin "2") (pinfunction "K_2") (pintype "passive"))
      (node (ref "LM1") (pin "1") (pinfunction "GND_1") (pintype "power_in"))
      (node (ref "LM2") (pin "1") (pinfunction "GND_1") (pintype "power_in"))
      (node (ref "P1") (pin "2") (pinfunction "2_2") (pintype "passive"))
      (node (ref "R5") (pin "1") (pinfunction "1_1") (pintype "passive"))
      (node (ref "ROCKER1") (pin "1") (pinfunction "1_1") (pintype "passive"))
      (node (ref "Reset1") (pin "2") (pinfunction "2_2") (pintype "passive"))
      (node (ref "S2") (pin "1") (pinfunction "1_1") (pintype "passive"))
      (node (ref "S3") (pin "1") (pinfunction "1_1") (pintype "passive"))
      (node (ref "S4") (pin "1") (pinfunction "1_1") (pintype "passive"))
      (node (ref "SD1") (pin "10") (pinfunction "GND_10") (pintype "passive"))
      (node (ref "SD1") (pin "6") (pinfunction "VSS_6") (pintype "passive"))
      (node (ref "U1") (pin "107") (pinfunction "VSS_2_107") (pintype "power_in"))
      (node (ref "U1") (pin "120") (pinfunction "VSS_10_120") (pintype "power_in"))
      (node (ref "U1") (pin "130") (pinfunction "VSS_11_130") (pintype "power_in"))
      (node (ref "U1") (pin "138") (pinfunction "BOOT0_138") (pintype "input"))
      (node (ref "U1") (pin "143") (pinfunction "VSS_3_143") (pintype "power_in"))
      (node (ref "U1") (pin "16") (pinfunction "VSS_5_16") (pintype "power_in"))
      (node (ref "U1") (pin "30") (pinfunction "VSSA_30") (pintype "power_in"))
      (node (ref "U1") (pin "31") (pinfunction "VREF-_31") (pintype "power_in"))
      (node (ref "U1") (pin "38") (pinfunction "VSS_4_38") (pintype "power_in"))
      (node (ref "U1") (pin "51") (pinfunction "VSS_6_51") (pintype "power_in"))
      (node (ref "U1") (pin "61") (pinfunction "VSS_7_61") (pintype "power_in"))
      (node (ref "U1") (pin "71") (pinfunction "VSS_1_71") (pintype "power_in"))
      (node (ref "U1") (pin "83") (pinfunction "VSS_8_83") (pintype "power_in"))
      (node (ref "U1") (pin "94") (pinfunction "VSS_9_94") (pintype "power_in"))
      (node (ref "UART") (pin "2") (pinfunction "2_2") (pintype "passive"))
    )
    (net (code "78") (name "Net-(DC1-PadVCC)") (class "Default")
      (node (ref "DC1") (pin "VCC") (pinfunction "VCC_VCC") (pintype "passive"))
      (node (ref "S1") (pin "1") (pinfunction "1_1") (pintype "passive"))
      (node (ref "S1") (pin "4") (pinfunction "4_4") (pintype "passive"))
    )
    (net (code "79") (name "Net-(LED1-A)") (class "Default")
      (node (ref "LED1") (pin "1") (pinfunction "A_1") (pintype "passive"))
      (node (ref "R6") (pin "1") (pinfunction "1_1") (pintype "passive"))
    )
    (net (code "80") (name "Net-(LED2-A)") (class "Default")
      (node (ref "LED2") (pin "1") (pinfunction "A_1") (pintype "passive"))
      (node (ref "R7") (pin "1") (pinfunction "1_1") (pintype "passive"))
    )
    (net (code "81") (name "VBAT") (class "Default")
      (node (ref "BT1") (pin "1") (pinfunction "+_1") (pintype "passive"))
      (node (ref "U1") (pin "6") (pinfunction "VBAT_6") (pintype "power_in"))
    )
    (net (code "82") (name "VDDA") (class "Default")
      (node (ref "C8") (pin "2") (pinfunction "2_2") (pintype "passive"))
      (node (ref "C9") (pin "2") (pinfunction "2_2") (pintype "passive"))
      (node (ref "L1") (pin "2") (pinfunction "2_2") (pintype "passive"))
      (node (ref "U1") (pin "32") (pinfunction "VREF+_32") (pintype "power_in"))
      (node (ref "U1") (pin "33") (pinfunction "VDDA_33") (pintype "power_in"))
    )
    (net (code "83") (name "unconnected-(JTAG-Pad11)") (class "Default")
      (node (ref "JTAG") (pin "11") (pinfunction "11_11") (pintype "passive"))
    )
    (net (code "84") (name "unconnected-(JTAG-Pad17)") (class "Default")
      (node (ref "JTAG") (pin "17") (pinfunction "17_17") (pintype "passive"))
    )
    (net (code "85") (name "unconnected-(JTAG-Pad19)") (class "Default")
      (node (ref "JTAG") (pin "19") (pinfunction "19_19") (pintype "passive"))
    )
    (net (code "86") (name "unconnected-(LCD-Pad28)") (class "Default")
      (node (ref "LCD") (pin "28") (pinfunction "28_28") (pintype "passive+no_connect"))
    )
    (net (code "87") (name "unconnected-(LCD-Pad30)") (class "Default")
      (node (ref "LCD") (pin "30") (pinfunction "30_30") (pintype "passive+no_connect"))
    )
    (net (code "88") (name "unconnected-(LCD-Pad32)") (class "Default")
      (node (ref "LCD") (pin "32") (pinfunction "32_32") (pintype "passive+no_connect"))
    )
    (net (code "89") (name "unconnected-(S1-Pad3)") (class "Default")
      (node (ref "S1") (pin "3") (pinfunction "3_3") (pintype "passive"))
    )
    (net (code "90") (name "unconnected-(S1-Pad6)") (class "Default")
      (node (ref "S1") (pin "6") (pinfunction "6_6") (pintype "passive"))
    )
    (net (code "91") (name "unconnected-(SD1-K-Pad9)") (class "Default")
      (node (ref "SD1") (pin "9") (pinfunction "K_9") (pintype "passive"))
    )
    (net (code "92") (name "unconnected-(U1A-PA0-WKUP-Pad34)") (class "Default")
      (node (ref "U1") (pin "34") (pinfunction "PA0-WKUP_34") (pintype "bidirectional"))
    )
    (net (code "93") (name "unconnected-(U1A-PA3-Pad37)") (class "Default")
      (node (ref "U1") (pin "37") (pinfunction "PA3_37") (pintype "bidirectional"))
    )
    (net (code "94") (name "unconnected-(U1A-PA4-Pad40)") (class "Default")
      (node (ref "U1") (pin "40") (pinfunction "PA4_40") (pintype "bidirectional"))
    )
    (net (code "95") (name "unconnected-(U1A-PA12-Pad104)") (class "Default")
      (node (ref "U1") (pin "104") (pinfunction "PA12_104") (pintype "bidirectional"))
    )
    (net (code "96") (name "unconnected-(U1A-PB5-Pad135)") (class "Default")
      (node (ref "U1") (pin "135") (pinfunction "PB5_135") (pintype "bidirectional"))
    )
    (net (code "97") (name "unconnected-(U1A-PB7-Pad137)") (class "Default")
      (node (ref "U1") (pin "137") (pinfunction "PB7_137") (pintype "bidirectional"))
    )
    (net (code "98") (name "unconnected-(U1A-PB8-Pad139)") (class "Default")
      (node (ref "U1") (pin "139") (pinfunction "PB8_139") (pintype "bidirectional"))
    )
    (net (code "99") (name "unconnected-(U1A-PB9-Pad140)") (class "Default")
      (node (ref "U1") (pin "140") (pinfunction "PB9_140") (pintype "bidirectional"))
    )
    (net (code "100") (name "unconnected-(U1A-PB12-Pad73)") (class "Default")
      (node (ref "U1") (pin "73") (pinfunction "PB12_73") (pintype "bidirectional"))
    )
    (net (code "101") (name "unconnected-(U1A-PB13-Pad74)") (class "Default")
      (node (ref "U1") (pin "74") (pinfunction "PB13_74") (pintype "bidirectional"))
    )
    (net (code "102") (name "unconnected-(U1A-PB14-Pad75)") (class "Default")
      (node (ref "U1") (pin "75") (pinfunction "PB14_75") (pintype "bidirectional"))
    )
    (net (code "103") (name "unconnected-(U1A-PB15-Pad76)") (class "Default")
      (node (ref "U1") (pin "76") (pinfunction "PB15_76") (pintype "bidirectional"))
    )
    (net (code "104") (name "unconnected-(U1A-PC13-TAMPER-RTC-Pad7)") (class "Default")
      (node (ref "U1") (pin "7") (pinfunction "PC13-TAMPER-RTC_7") (pintype "bidirectional"))
    )
    (net (code "105") (name "unconnected-(U1A-PC14-OSC32_IN-Pad8)") (class "Default")
      (node (ref "U1") (pin "8") (pinfunction "PC14-OSC32_IN_8") (pintype "bidirectional"))
    )
    (net (code "106") (name "unconnected-(U1A-PC15-OSC32_OUT-Pad9)") (class "Default")
      (node (ref "U1") (pin "9") (pinfunction "PC15-OSC32_OUT_9") (pintype "bidirectional"))
    )
    (net (code "107") (name "unconnected-(U1A-PD3-Pad117)") (class "Default")
      (node (ref "U1") (pin "117") (pinfunction "PD3_117") (pintype "bidirectional"))
    )
    (net (code "108") (name "unconnected-(U1A-PD6-Pad122)") (class "Default")
      (node (ref "U1") (pin "122") (pinfunction "PD6_122") (pintype "bidirectional"))
    )
    (net (code "109") (name "unconnected-(U1A-PD7-Pad123)") (class "Default")
      (node (ref "U1") (pin "123") (pinfunction "PD7_123") (pintype "bidirectional"))
    )
    (net (code "110") (name "unconnected-(U1B-NC-Pad106)") (class "Default")
      (node (ref "U1") (pin "106") (pinfunction "NC_106") (pintype "passive"))
    )
    (net (code "111") (name "unconnected-(U1B-PE0-Pad141)") (class "Default")
      (node (ref "U1") (pin "141") (pinfunction "PE0_141") (pintype "bidirectional"))
    )
    (net (code "112") (name "unconnected-(U1B-PE1-Pad142)") (class "Default")
      (node (ref "U1") (pin "142") (pinfunction "PE1_142") (pintype "bidirectional"))
    )
    (net (code "113") (name "unconnected-(U1B-PE2-Pad1)") (class "Default")
      (node (ref "U1") (pin "1") (pinfunction "PE2_1") (pintype "bidirectional"))
    )
    (net (code "114") (name "unconnected-(U1B-PE3-Pad2)") (class "Default")
      (node (ref "U1") (pin "2") (pinfunction "PE3_2") (pintype "bidirectional"))
    )
    (net (code "115") (name "unconnected-(U1B-PE4-Pad3)") (class "Default")
      (node (ref "U1") (pin "3") (pinfunction "PE4_3") (pintype "bidirectional"))
    )
    (net (code "116") (name "unconnected-(U1B-PE5-Pad4)") (class "Default")
      (node (ref "U1") (pin "4") (pinfunction "PE5_4") (pintype "bidirectional"))
    )
    (net (code "117") (name "unconnected-(U1B-PE6-Pad5)") (class "Default")
      (node (ref "U1") (pin "5") (pinfunction "PE6_5") (pintype "bidirectional"))
    )
    (net (code "118") (name "unconnected-(U1B-PF0-Pad10)") (class "Default")
      (node (ref "U1") (pin "10") (pinfunction "PF0_10") (pintype "bidirectional"))
    )
    (net (code "119") (name "unconnected-(U1B-PF1-Pad11)") (class "Default")
      (node (ref "U1") (pin "11") (pinfunction "PF1_11") (pintype "bidirectional"))
    )
    (net (code "120") (name "unconnected-(U1B-PF2-Pad12)") (class "Default")
      (node (ref "U1") (pin "12") (pinfunction "PF2_12") (pintype "bidirectional"))
    )
    (net (code "121") (name "unconnected-(U1B-PF3-Pad13)") (class "Default")
      (node (ref "U1") (pin "13") (pinfunction "PF3_13") (pintype "bidirectional"))
    )
    (net (code "122") (name "unconnected-(U1B-PF4-Pad14)") (class "Default")
      (node (ref "U1") (pin "14") (pinfunction "PF4_14") (pintype "bidirectional"))
    )
    (net (code "123") (name "unconnected-(U1B-PF11-Pad49)") (class "Default")
      (node (ref "U1") (pin "49") (pinfunction "PF11_49") (pintype "bidirectional"))
    )
    (net (code "124") (name "unconnected-(U1B-PF12-Pad50)") (class "Default")
      (node (ref "U1") (pin "50") (pinfunction "PF12_50") (pintype "bidirectional"))
    )
    (net (code "125") (name "unconnected-(U1B-PF13-Pad53)") (class "Default")
      (node (ref "U1") (pin "53") (pinfunction "PF13_53") (pintype "bidirectional"))
    )
    (net (code "126") (name "unconnected-(U1B-PF14-Pad54)") (class "Default")
      (node (ref "U1") (pin "54") (pinfunction "PF14_54") (pintype "bidirectional"))
    )
    (net (code "127") (name "unconnected-(U1B-PF15-Pad55)") (class "Default")
      (node (ref "U1") (pin "55") (pinfunction "PF15_55") (pintype "bidirectional"))
    )
    (net (code "128") (name "unconnected-(U1B-PG1-Pad57)") (class "Default")
      (node (ref "U1") (pin "57") (pinfunction "PG1_57") (pintype "bidirectional"))
    )
    (net (code "129") (name "unconnected-(U1B-PG9-Pad124)") (class "Default")
      (node (ref "U1") (pin "124") (pinfunction "PG9_124") (pintype "bidirectional"))
    )
    (net (code "130") (name "unconnected-(U1B-PG10-Pad125)") (class "Default")
      (node (ref "U1") (pin "125") (pinfunction "PG10_125") (pintype "bidirectional"))
    )
    (net (code "131") (name "unconnected-(U1B-PG11-Pad126)") (class "Default")
      (node (ref "U1") (pin "126") (pinfunction "PG11_126") (pintype "bidirectional"))
    )
    (net (code "132") (name "unconnected-(U1B-PG13-Pad128)") (class "Default")
      (node (ref "U1") (pin "128") (pinfunction "PG13_128") (pintype "bidirectional"))
    )
    (net (code "133") (name "unconnected-(U1B-PG14-Pad129)") (class "Default")
      (node (ref "U1") (pin "129") (pinfunction "PG14_129") (pintype "bidirectional"))
    )
    (net (code "134") (name "unconnected-(U1B-PG15-Pad132)") (class "Default")
      (node (ref "U1") (pin "132") (pinfunction "PG15_132") (pintype "bidirectional"))
    )
  )
)
